# SHEET4.net
KiCad netlist of a schematic drawn in Altium Designer
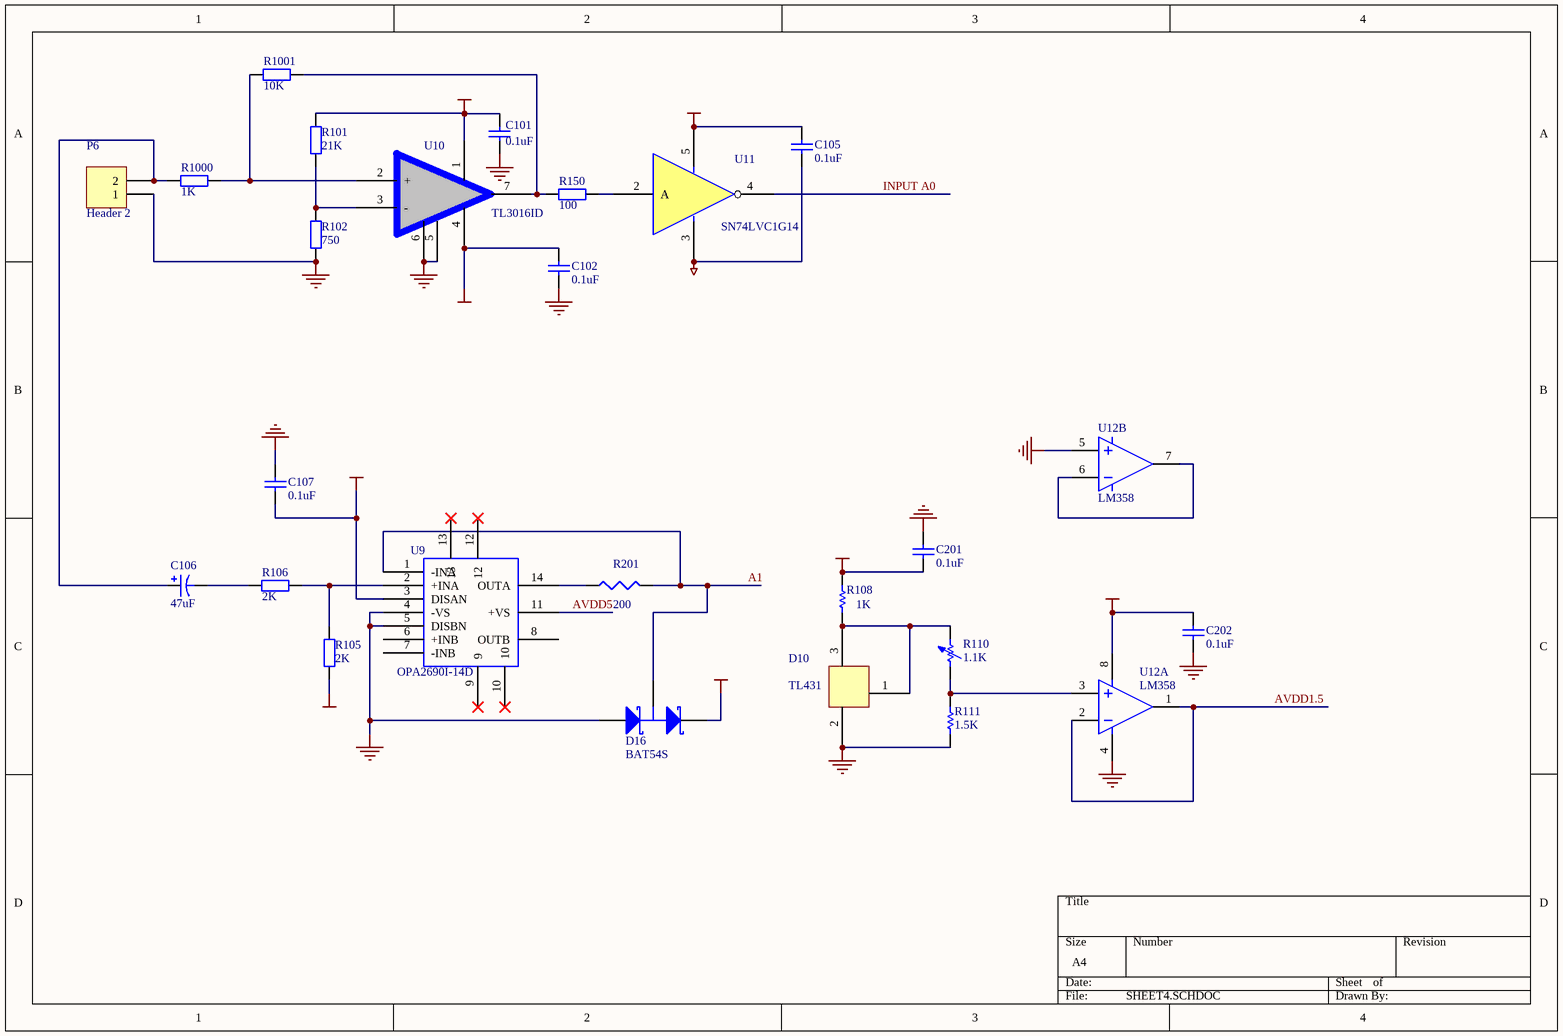
[diagram p0: SHEET4.SCHDOC]

(export (version "E")
  (design (tool "Eeschema 10.0.6"))
  (components
    (comp (ref "C101")
      (value "0.1uF")
      (footprint "CC2012-0805")
      (description "Capacitor")
      (fields (field (name "PUBLISHER") "Altium Limited"))
      (libsource (lib "Miscellaneous Devices") (part "Cap"))
    )
    (comp (ref "C102")
      (value "0.1uF")
      (footprint "CC2012-0805")
      (description "Capacitor")
      (fields (field (name "PUBLISHER") "Altium Limited"))
      (libsource (lib "Miscellaneous Devices") (part "Cap"))
    )
    (comp (ref "C105")
      (value "0.1uF")
      (footprint "CC2012-0805")
      (description "Capacitor")
      (fields (field (name "PUBLISHER") "Altium Limited"))
      (libsource (lib "Miscellaneous Devices") (part "Cap"))
    )
    (comp (ref "C106")
      (value "47uF")
      (footprint "CA2522-0612")
      (description "Polarized Capacitor (Surface Mount)")
      (fields (field (name "PUBLISHER") "Altium Limited"))
      (libsource (lib "Miscellaneous Devices") (part "Cap Pol3"))
    )
    (comp (ref "C107")
      (value "0.1uF")
      (footprint "CC2012-0805")
      (description "Capacitor")
      (fields (field (name "PUBLISHER") "Altium Limited"))
      (libsource (lib "Miscellaneous Devices") (part "Cap"))
    )
    (comp (ref "C201")
      (value "0.1uF")
      (footprint "CC2012-0805")
      (description "Capacitor (Semiconductor SIM Model)")
      (fields (field (name "PUBLISHER") "Altium Limited"))
      (libsource (lib "Miscellaneous Devices") (part "Cap Semi"))
    )
    (comp (ref "C202")
      (value "0.1uF")
      (footprint "CC2012-0805")
      (description "Capacitor (Semiconductor SIM Model)")
      (fields (field (name "PUBLISHER") "Altium Limited"))
      (libsource (lib "Miscellaneous Devices") (part "Cap Semi"))
    )
    (comp (ref "D10") (value "TL431") (footprint "BCY-W3") (libsource (lib "Schlib1") (part "TL431")))
    (comp (ref "D16")
      (value "BAT54S")
      (footprint "SOT23")
      (description "Schottky Barrier Double Diode")
      (fields (field (name "PUBLISHER") "Altium Limited"))
      (libsource (lib "Philips Discrete Diode - Schottky") (part "BAT54S"))
    )
    (comp (ref "P6")
      (value "Header 2")
      (footprint "5.08_A")
      (description "Header, 2-Pin")
      (fields (field (name "PUBLISHER") "Altium Limited"))
      (libsource (lib "Miscellaneous Connectors") (part "Header 2"))
    )
    (comp (ref "R101")
      (value "21K")
      (footprint "CR2012-0805")
      (description "Resistor")
      (fields (field (name "PUBLISHER") "Altium Limited"))
      (libsource (lib "Miscellaneous Devices") (part "Res2"))
    )
    (comp (ref "R102")
      (value "750")
      (footprint "CR2012-0805")
      (description "Resistor")
      (fields (field (name "PUBLISHER") "Altium Limited"))
      (libsource (lib "Miscellaneous Devices") (part "Res2"))
    )
    (comp (ref "R105")
      (value "2K")
      (footprint "CR2012-0805")
      (description "Resistor")
      (fields (field (name "PUBLISHER") "Altium Limited"))
      (libsource (lib "Miscellaneous Devices") (part "Res2"))
    )
    (comp (ref "R106")
      (value "2K")
      (footprint "CR2012-0805")
      (description "Resistor")
      (fields (field (name "PUBLISHER") "Altium Limited"))
      (libsource (lib "") (part "Res2_1"))
    )
    (comp (ref "R108")
      (value "1K")
      (footprint "CR2012-0805")
      (description "Resistor")
      (fields (field (name "PUBLISHER") "Altium Limited"))
      (libsource (lib "Miscellaneous Devices") (part "Res1"))
    )
    (comp (ref "R110")
      (value "1.1K")
      (footprint "CR2012-0805")
      (description "Variable Resistor")
      (fields (field (name "PUBLISHER") "Altium Limited"))
      (libsource (lib "Miscellaneous Devices") (part "Res Adj1"))
    )
    (comp (ref "R111")
      (value "1.5K")
      (footprint "CR2012-0805")
      (description "Resistor")
      (fields (field (name "PUBLISHER") "Altium Limited"))
      (libsource (lib "Miscellaneous Devices") (part "Res1"))
    )
    (comp (ref "R150")
      (value "100")
      (footprint "CR2012-0805")
      (description "Resistor")
      (fields (field (name "PUBLISHER") "Altium Limited"))
      (libsource (lib "") (part "Res2_1"))
    )
    (comp (ref "R201")
      (value "200")
      (footprint "CR2012-0805")
      (description "Resistor")
      (fields (field (name "PUBLISHER") "Altium Limited"))
      (libsource (lib "Miscellaneous Devices") (part "Res3"))
    )
    (comp (ref "R1000")
      (value "1K")
      (footprint "CR2012-0805")
      (description "Resistor")
      (fields (field (name "PUBLISHER") "Altium Limited"))
      (libsource (lib "") (part "Res2_1"))
    )
    (comp (ref "R1001")
      (value "10K")
      (footprint "CR2012-0805")
      (description "Resistor")
      (fields (field (name "PUBLISHER") "Altium Limited"))
      (libsource (lib "") (part "Res2_1"))
    )
    (comp (ref "U9")
      (value "OPA2690I-14D")
      (footprint "SOP14")
      (libsource (lib "Schlib1") (part "OPA2690I-14D"))
    )
    (comp (ref "U10") (value "TL3016ID") (footprint "PcbLib1:SOP8") (libsource (lib "*") (part "TL3016ID")))
    (comp (ref "U11")
      (value "SN74LVC1G14")
      (footprint "SC-70")
      (libsource (lib "MyIntLib") (part "SN74LVC1G14"))
    )
    (comp (ref "U12") (value "LM358") (footprint "SO-8") (libsource (lib "mydevices") (part "LF353")))
  )
  (nets
    (net (code "1") (name "/A1") (class "Default")
      (node (ref "D16") (pin "3") (pinfunction "C_3") (pintype "passive"))
      (node (ref "R201") (pin "2") (pinfunction "2_2") (pintype "passive"))
      (node (ref "U9") (pin "1") (pinfunction "-INA_1") (pintype "passive"))
    )
    (net (code "2") (name "/INPUT A0") (class "Default")
      (node (ref "U11") (pin "4") (pinfunction "Y_4") (pintype "passive"))
    )
    (net (code "3") (name "3.3V") (class "Default")
      (node (ref "C105") (pin "2") (pinfunction "2_2") (pintype "passive"))
      (node (ref "U11") (pin "5") (pinfunction "VCC_5") (pintype "power_in"))
    )
    (net (code "4") (name "ADIOA3.3") (class "Default")
      (node (ref "D16") (pin "2") (pinfunction "K_2") (pintype "passive"))
    )
    (net (code "5") (name "AGND") (class "Default")
      (node (ref "C101") (pin "2") (pinfunction "2_2") (pintype "passive"))
      (node (ref "C102") (pin "1") (pinfunction "1_1") (pintype "passive"))
      (node (ref "C107") (pin "2") (pinfunction "2_2") (pintype "passive"))
      (node (ref "C201") (pin "2") (pinfunction "2_2") (pintype "passive"))
      (node (ref "C202") (pin "1") (pinfunction "1_1") (pintype "passive"))
      (node (ref "D10") (pin "2") (pinfunction "2_2") (pintype "passive"))
      (node (ref "D16") (pin "1") (pinfunction "A_1") (pintype "passive"))
      (node (ref "P6") (pin "1") (pinfunction "1_1") (pintype "passive"))
      (node (ref "R102") (pin "1") (pinfunction "1_1") (pintype "passive"))
      (node (ref "R111") (pin "1") (pinfunction "1_1") (pintype "passive"))
      (node (ref "U10") (pin "5") (pinfunction "5_5") (pintype "passive"))
      (node (ref "U10") (pin "6") (pinfunction "6_6") (pintype "passive"))
      (node (ref "U12") (pin "4") (pintype "passive"))
      (node (ref "U12") (pin "5") (pintype "passive"))
      (node (ref "U9") (pin "4") (pinfunction "-VS_4") (pintype "passive"))
      (node (ref "U9") (pin "5") (pinfunction "DISBN_5") (pintype "passive"))
    )
    (net (code "6") (name "AVDD1.5") (class "Default")
      (node (ref "R105") (pin "1") (pinfunction "1_1") (pintype "passive"))
      (node (ref "U12") (pin "1") (pintype "passive"))
      (node (ref "U12") (pin "2") (pintype "passive"))
    )
    (net (code "7") (name "AVDD5") (class "Default")
      (node (ref "C101") (pin "1") (pinfunction "1_1") (pintype "passive"))
      (node (ref "C107") (pin "1") (pinfunction "1_1") (pintype "passive"))
      (node (ref "C201") (pin "1") (pinfunction "1_1") (pintype "passive"))
      (node (ref "C202") (pin "2") (pinfunction "2_2") (pintype "passive"))
      (node (ref "R101") (pin "2") (pinfunction "2_2") (pintype "passive"))
      (node (ref "R108") (pin "2") (pinfunction "2_2") (pintype "passive"))
      (node (ref "U10") (pin "1") (pinfunction "1_1") (pintype "passive"))
      (node (ref "U12") (pin "8") (pintype "passive"))
      (node (ref "U9") (pin "11") (pinfunction "+VS_11") (pintype "passive"))
      (node (ref "U9") (pin "3") (pinfunction "DISAN_3") (pintype "passive"))
    )
    (net (code "8") (name "AVDD5N") (class "Default")
      (node (ref "C102") (pin "2") (pinfunction "2_2") (pintype "passive"))
      (node (ref "U10") (pin "4") (pinfunction "4_4") (pintype "passive"))
    )
    (net (code "9") (name "DGND") (class "Default")
      (node (ref "C105") (pin "1") (pinfunction "1_1") (pintype "passive"))
      (node (ref "U11") (pin "3") (pinfunction "GND_3") (pintype "power_in"))
    )
    (net (code "10") (name "Net-(C106-Pad1)") (class "Default")
      (node (ref "C106") (pin "1") (pinfunction "1_1") (pintype "passive"))
      (node (ref "P6") (pin "2") (pinfunction "2_2") (pintype "passive"))
      (node (ref "R1000") (pin "1") (pinfunction "1_1") (pintype "passive"))
    )
    (net (code "11") (name "Net-(C106-Pad2)") (class "Default")
      (node (ref "C106") (pin "2") (pinfunction "2_2") (pintype "passive"))
      (node (ref "R106") (pin "1") (pinfunction "1_1") (pintype "passive"))
    )
    (net (code "12") (name "Net-(D10-Pad1)") (class "Default")
      (node (ref "D10") (pin "1") (pinfunction "1_1") (pintype "passive"))
      (node (ref "D10") (pin "3") (pinfunction "3_3") (pintype "passive"))
      (node (ref "R108") (pin "1") (pinfunction "1_1") (pintype "passive"))
      (node (ref "R110") (pin "2") (pinfunction "2_2") (pintype "passive"))
    )
    (net (code "13") (name "Net-(R110-Pad1)") (class "Default")
      (node (ref "R110") (pin "1") (pinfunction "1_1") (pintype "passive"))
      (node (ref "R111") (pin "2") (pinfunction "2_2") (pintype "passive"))
      (node (ref "U12") (pin "3") (pintype "passive"))
    )
    (net (code "14") (name "Net-(R1001-Pad2)") (class "Default")
      (node (ref "R1001") (pin "2") (pinfunction "2_2") (pintype "passive"))
      (node (ref "R150") (pin "1") (pinfunction "1_1") (pintype "passive"))
      (node (ref "U10") (pin "7") (pinfunction "7_7") (pintype "passive"))
    )
    (net (code "15") (name "Net-(U9-+INA)") (class "Default")
      (node (ref "R105") (pin "2") (pinfunction "2_2") (pintype "passive"))
      (node (ref "R106") (pin "2") (pinfunction "2_2") (pintype "passive"))
      (node (ref "U9") (pin "2") (pinfunction "+INA_2") (pintype "passive"))
    )
    (net (code "16") (name "Net-(U9-OUTA)") (class "Default")
      (node (ref "R201") (pin "1") (pinfunction "1_1") (pintype "passive"))
      (node (ref "U9") (pin "14") (pinfunction "OUTA_14") (pintype "passive"))
    )
    (net (code "17") (name "Net-(U10-+)") (class "Default")
      (node (ref "R1000") (pin "2") (pinfunction "2_2") (pintype "passive"))
      (node (ref "R1001") (pin "1") (pinfunction "1_1") (pintype "passive"))
      (node (ref "U10") (pin "2") (pinfunction "+_2") (pintype "passive"))
    )
    (net (code "18") (name "Net-(U10--)") (class "Default")
      (node (ref "R101") (pin "1") (pinfunction "1_1") (pintype "passive"))
      (node (ref "R102") (pin "2") (pinfunction "2_2") (pintype "passive"))
      (node (ref "U10") (pin "3") (pinfunction "-_3") (pintype "passive"))
    )
    (net (code "19") (name "Net-(U11-A)") (class "Default")
      (node (ref "R150") (pin "2") (pinfunction "2_2") (pintype "passive"))
      (node (ref "U11") (pin "2") (pinfunction "A_2") (pintype "passive"))
    )
    (net (code "20") (name "Net-(U12-Pad6)") (class "Default")
      (node (ref "U12") (pin "6") (pintype "passive"))
      (node (ref "U12") (pin "7") (pintype "passive"))
    )
    (net (code "21") (name "unconnected-(U9-+INB-Pad6)") (class "Default")
      (node (ref "U9") (pin "6") (pinfunction "+INB_6") (pintype "passive"))
    )
    (net (code "22") (name "unconnected-(U9--INB-Pad7)") (class "Default")
      (node (ref "U9") (pin "7") (pinfunction "-INB_7") (pintype "passive"))
    )
    (net (code "23") (name "unconnected-(U9-OUTB-Pad8)") (class "Default")
      (node (ref "U9") (pin "8") (pinfunction "OUTB_8") (pintype "passive"))
    )
    (net (code "24") (name "unconnected-(U9-Pad9)") (class "Default")
      (node (ref "U9") (pin "9") (pinfunction "9_9") (pintype "passive+no_connect"))
    )
    (net (code "25") (name "unconnected-(U9-Pad10)") (class "Default")
      (node (ref "U9") (pin "10") (pinfunction "10_10") (pintype "passive+no_connect"))
    )
    (net (code "26") (name "unconnected-(U9-Pad12)") (class "Default")
      (node (ref "U9") (pin "12") (pinfunction "12_12") (pintype "passive+no_connect"))
    )
    (net (code "27") (name "unconnected-(U9-Pad13)") (class "Default")
      (node (ref "U9") (pin "13") (pinfunction "13_13") (pintype "passive+no_connect"))
    )
    (net (code "28") (name "unconnected-(U11-NC-Pad1)") (class "Default")
      (node (ref "U11") (pin "1") (pinfunction "NC_1") (pintype "passive"))
    )
  )
)
